# MARLIN.net
KiCad netlist of a schematic drawn in Altium Designer
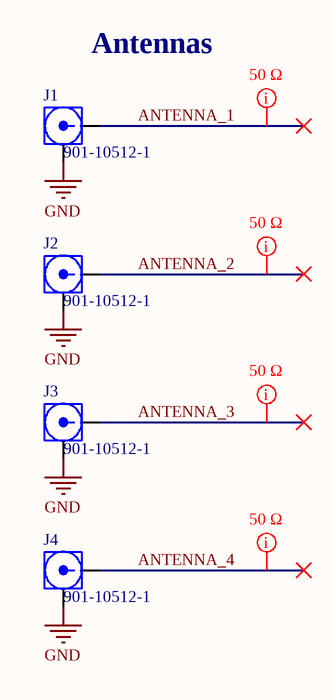
[diagram p0: MARLIN.SchDoc]

(export (version "E")
  (design (tool "Eeschema 10.0.6"))
  (components
    (comp (ref "J1")
      (value "901-10512-1")
      (footprint "901-10512-1")
      (description "RF / Coaxial Connector, SMA Coaxial, Straight Flanged Jack, Solder, 50 ohm, Beryllium Copper")
      (fields (field (name "MANUFACTURER") "Amphenol"))
      (libsource (lib "Titan") (part "901-10512-1"))
    )
    (comp (ref "J2")
      (value "901-10512-1")
      (footprint "901-10512-1")
      (description "RF / Coaxial Connector, SMA Coaxial, Straight Flanged Jack, Solder, 50 ohm, Beryllium Copper")
      (fields (field (name "MANUFACTURER") "Amphenol"))
      (libsource (lib "Titan") (part "901-10512-1"))
    )
    (comp (ref "J3")
      (value "901-10512-1")
      (footprint "901-10512-1")
      (description "RF / Coaxial Connector, SMA Coaxial, Straight Flanged Jack, Solder, 50 ohm, Beryllium Copper")
      (fields (field (name "MANUFACTURER") "Amphenol"))
      (libsource (lib "Titan") (part "901-10512-1"))
    )
    (comp (ref "J4")
      (value "901-10512-1")
      (footprint "901-10512-1")
      (description "RF / Coaxial Connector, SMA Coaxial, Straight Flanged Jack, Solder, 50 ohm, Beryllium Copper")
      (fields (field (name "MANUFACTURER") "Amphenol"))
      (libsource (lib "Titan") (part "901-10512-1"))
    )
  )
  (nets
    (net (code "1") (name "/ANTENNA_1") (class "Default")
      (node (ref "J1") (pin "1") (pintype "passive+no_connect"))
    )
    (net (code "2") (name "/ANTENNA_2") (class "Default")
      (node (ref "J2") (pin "1") (pintype "passive+no_connect"))
    )
    (net (code "3") (name "/ANTENNA_3") (class "Default")
      (node (ref "J3") (pin "1") (pintype "passive+no_connect"))
    )
    (net (code "4") (name "/ANTENNA_4") (class "Default")
      (node (ref "J4") (pin "1") (pintype "passive+no_connect"))
    )
    (net (code "5") (name "GND") (class "Default")
      (node (ref "J1") (pin "2") (pintype "passive"))
      (node (ref "J2") (pin "2") (pintype "passive"))
      (node (ref "J3") (pin "2") (pintype "passive"))
      (node (ref "J4") (pin "2") (pintype "passive"))
    )
  )
)
